# GPS_radiologger_v20.net
KiCad netlist of a schematic drawn in EAGLE
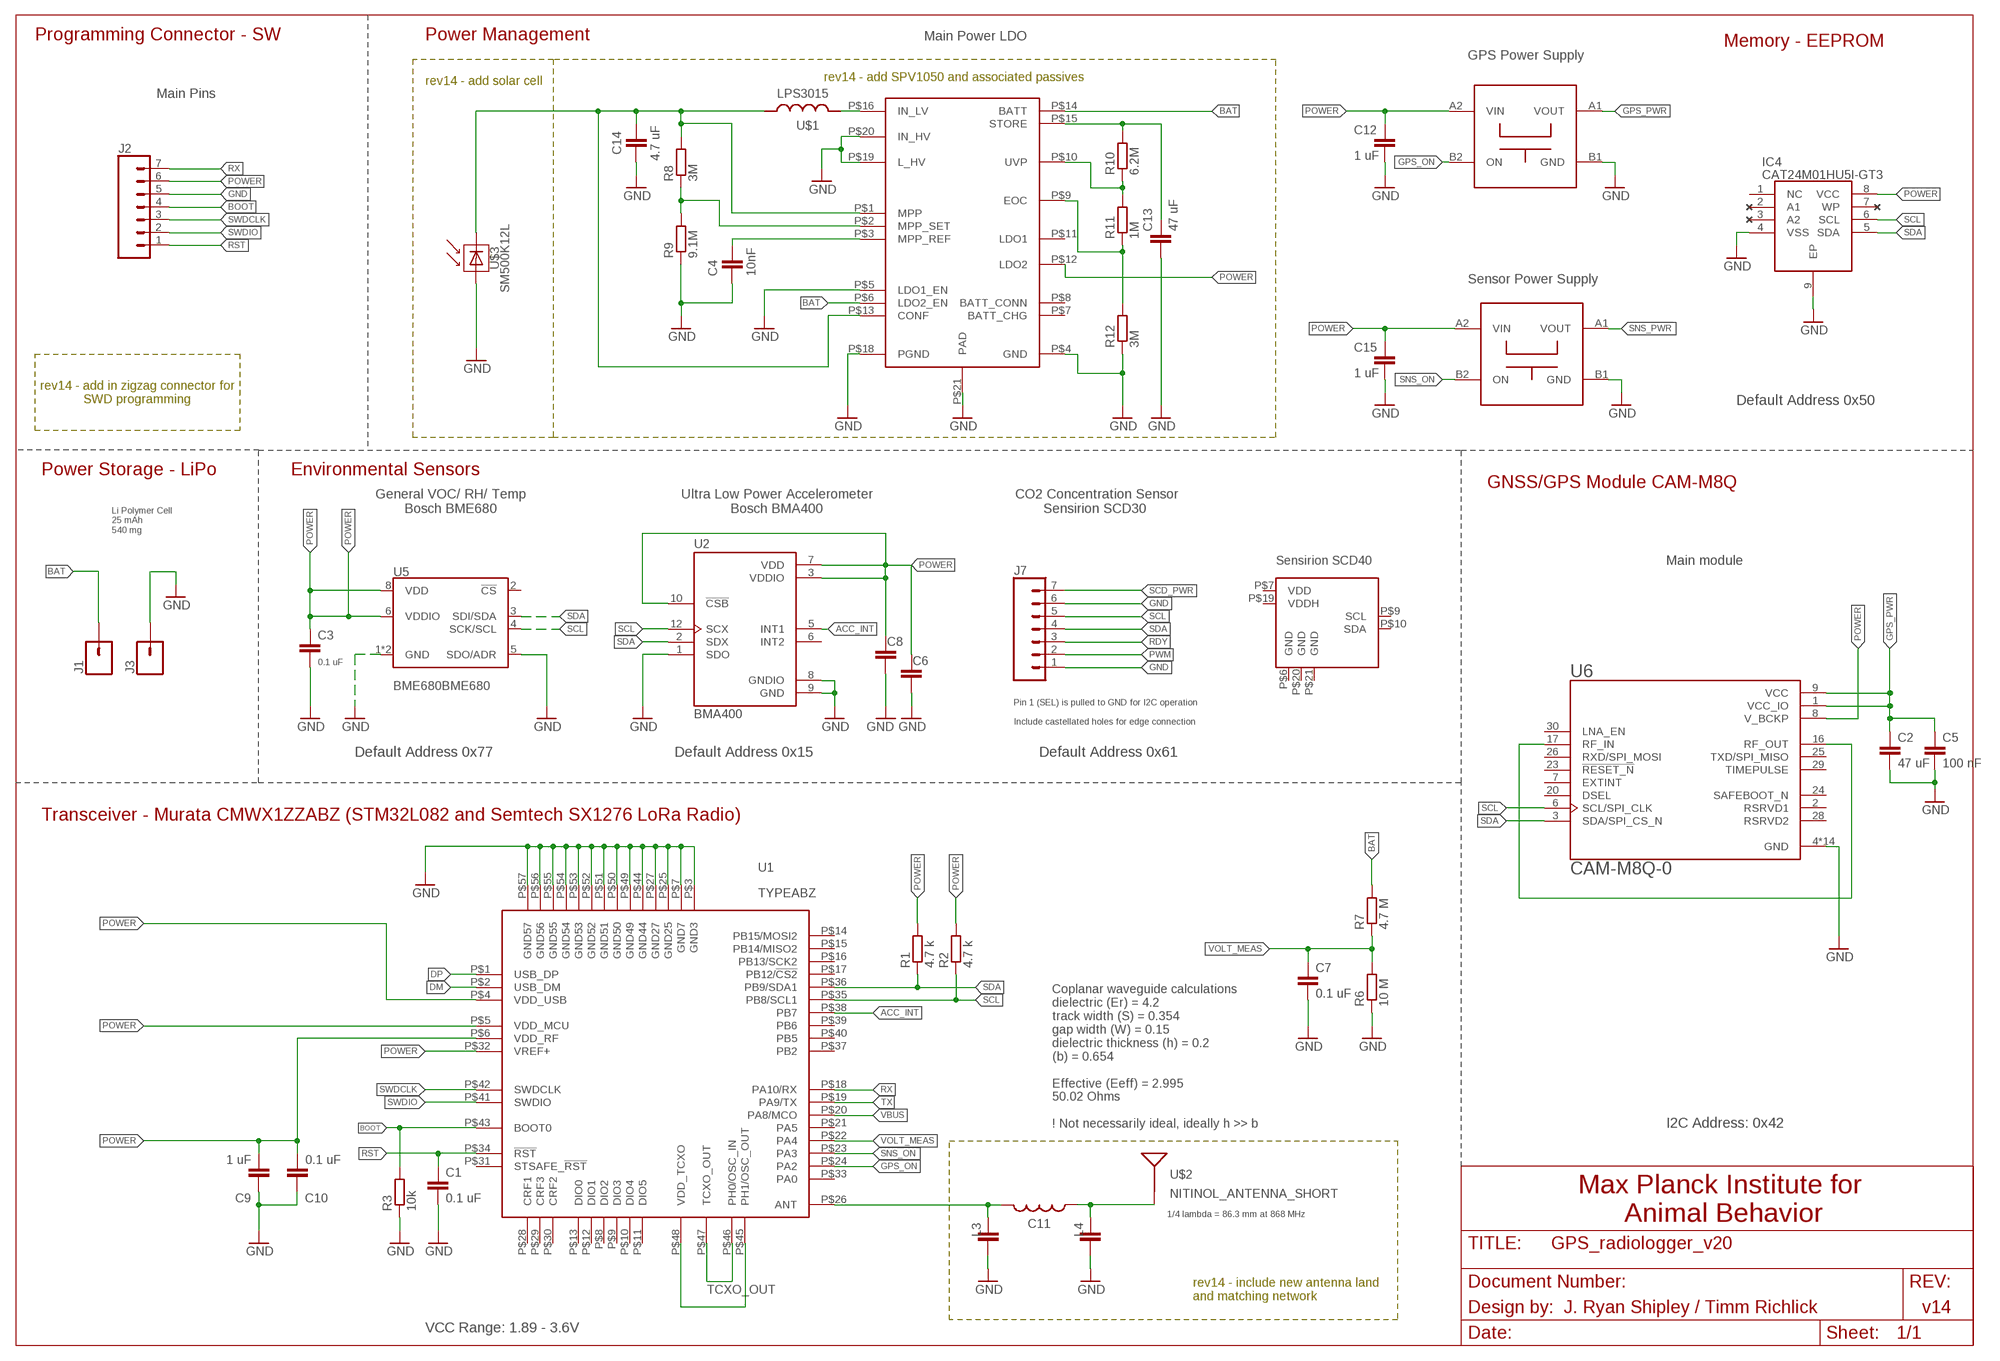
[diagram p0: schematic, sheet 1]

(export (version "E")
  (design (tool "Eeschema 10.0.6"))
  (components
    (comp (ref "C1")
      (value "0.1 uF")
      (footprint "eagle-import:C0201")
      (libsource (lib "eagle-import") (part "C-EUC0201"))
    )
    (comp (ref "C2")
      (value "47 uF")
      (footprint "eagle-import:C0201")
      (libsource (lib "eagle-import") (part "C-EUC0201"))
    )
    (comp (ref "C3")
      (value "0.1 uF")
      (footprint "eagle-import:C0201")
      (libsource (lib "eagle-import") (part "C-EUC0201"))
    )
    (comp (ref "C4")
      (value "10nF")
      (footprint "eagle-import:C0201")
      (libsource (lib "eagle-import") (part "C-EUC0201"))
    )
    (comp (ref "C5")
      (value "100 nF")
      (footprint "eagle-import:C0201")
      (libsource (lib "eagle-import") (part "C-EUC0201"))
    )
    (comp (ref "C6")
      (value "C-EUC0201")
      (footprint "eagle-import:C0201")
      (libsource (lib "eagle-import") (part "C-EUC0201"))
    )
    (comp (ref "C7")
      (value "0.1 uF")
      (footprint "eagle-import:C0201")
      (libsource (lib "eagle-import") (part "C-EUC0201"))
    )
    (comp (ref "C8")
      (value "C-EUC0201")
      (footprint "eagle-import:C0201")
      (libsource (lib "eagle-import") (part "C-EUC0201"))
    )
    (comp (ref "C9")
      (value "1 uF")
      (footprint "eagle-import:C0201")
      (libsource (lib "eagle-import") (part "C-EUC0201"))
    )
    (comp (ref "C10")
      (value "0.1 uF")
      (footprint "eagle-import:C0201")
      (libsource (lib "eagle-import") (part "C-EUC0201"))
    )
    (comp (ref "C11")
      (value "0.1uF")
      (footprint "eagle-import:L0201")
      (libsource (lib "eagle-import") (part "L-USL0201"))
    )
    (comp (ref "C12")
      (value "1 uF")
      (footprint "eagle-import:C0201")
      (libsource (lib "eagle-import") (part "C-EUC0201"))
    )
    (comp (ref "C13")
      (value "47 uF")
      (footprint "eagle-import:C0805K")
      (libsource (lib "eagle-import") (part "C-EUC0805K"))
    )
    (comp (ref "C14")
      (value "4.7 uF")
      (footprint "eagle-import:C0201")
      (libsource (lib "eagle-import") (part "C-EUC0201"))
    )
    (comp (ref "C15")
      (value "1 uF")
      (footprint "eagle-import:C0201")
      (libsource (lib "eagle-import") (part "C-EUC0201"))
    )
    (comp (ref "IC4")
      (value "CAT24M01HU5I-GT3")
      (footprint "eagle-import:SON50P300X200X55-9N")
      (fields
        (field (name "MOUSER_PART_NUMBER") "863-CAT24M01HU5I-GT3")
        (field (name "RS_PART_NUMBER") "7814831P")
      )
      (libsource (lib "eagle-import") (part "CAT24M01HU5I-GT3"))
    )
    (comp (ref "J1")
      (value "CONN_01PTH_NO_SILK_YES_STOP")
      (footprint "eagle-import:1X01_NO_SILK")
      (libsource (lib "eagle-import") (part "CONN_01PTH_NO_SILK_YES_STOP"))
    )
    (comp (ref "J2")
      (value "CONN_07NO_SILK")
      (footprint "eagle-import:1X07_NO_SILK")
      (libsource (lib "eagle-import") (part "CONN_07NO_SILK"))
    )
    (comp (ref "J3")
      (value "CONN_01PTH_NO_SILK_YES_STOP")
      (footprint "eagle-import:1X01_NO_SILK")
      (libsource (lib "eagle-import") (part "CONN_01PTH_NO_SILK_YES_STOP"))
    )
    (comp (ref "J7")
      (value "CONN_07NO_SILK")
      (footprint "eagle-import:1X07_NO_SILK")
      (libsource (lib "eagle-import") (part "CONN_07NO_SILK"))
    )
    (comp (ref "L3")
      (value "C-EUC0201")
      (footprint "eagle-import:C0201")
      (libsource (lib "eagle-import") (part "C-EUC0201"))
    )
    (comp (ref "L4")
      (value "C-EUC0201")
      (footprint "eagle-import:C0201")
      (libsource (lib "eagle-import") (part "C-EUC0201"))
    )
    (comp (ref "R1")
      (value "4.7 k")
      (footprint "eagle-import:R0201")
      (libsource (lib "eagle-import") (part "R-EU_R0201"))
    )
    (comp (ref "R2")
      (value "4.7 k")
      (footprint "eagle-import:R0201")
      (libsource (lib "eagle-import") (part "R-EU_R0201"))
    )
    (comp (ref "R3")
      (value "10k")
      (footprint "eagle-import:R0201")
      (libsource (lib "eagle-import") (part "R-EU_R0201"))
    )
    (comp (ref "R6")
      (value "10 M")
      (footprint "eagle-import:R0201")
      (libsource (lib "eagle-import") (part "R-EU_R0201"))
    )
    (comp (ref "R7")
      (value "4.7 M")
      (footprint "eagle-import:R0201")
      (libsource (lib "eagle-import") (part "R-EU_R0201"))
    )
    (comp (ref "R8")
      (value "3M")
      (footprint "eagle-import:R0201")
      (libsource (lib "eagle-import") (part "R-EU_R0201"))
    )
    (comp (ref "R9")
      (value "9.1M")
      (footprint "eagle-import:R0201")
      (libsource (lib "eagle-import") (part "R-EU_R0201"))
    )
    (comp (ref "R10")
      (value "6.2M")
      (footprint "eagle-import:R0201")
      (libsource (lib "eagle-import") (part "R-EU_R0201"))
    )
    (comp (ref "R11")
      (value "1M")
      (footprint "eagle-import:R0201")
      (libsource (lib "eagle-import") (part "R-EU_R0201"))
    )
    (comp (ref "R12")
      (value "3M")
      (footprint "eagle-import:R0201")
      (libsource (lib "eagle-import") (part "R-EU_R0201"))
    )
    (comp (ref "U$1")
      (value "LPS3015")
      (footprint "eagle-import:LPS_3015")
      (libsource (lib "eagle-import") (part "LPS3015"))
    )
    (comp (ref "U$2")
      (value "NITINOL_ANTENNA_SHORT")
      (footprint "eagle-import:ICARUS_NITINOL_ANTENNA_SHORT")
      (libsource (lib "eagle-import") (part "NITINOL_ANTENNA_SHORT"))
    )
    (comp (ref "U$3")
      (value "SM500K12L")
      (footprint "eagle-import:SM500K12L")
      (libsource (lib "eagle-import") (part "SM500K12L"))
    )
    (comp (ref "U$4")
      (value "TPS22916CL")
      (footprint "eagle-import:YFP0004-DSBGA")
      (libsource (lib "eagle-import") (part "TPS22916CL"))
    )
    (comp (ref "U$5")
      (value "TPS22916CL")
      (footprint "eagle-import:YFP0004-DSBGA")
      (libsource (lib "eagle-import") (part "TPS22916CL"))
    )
    (comp (ref "U$6")
      (value "SCD40")
      (footprint "eagle-import:SCD40_LGA")
      (libsource (lib "eagle-import") (part "SCD40"))
    )
    (comp (ref "U1")
      (value "TYPEABZ")
      (footprint "eagle-import:TYPEABZ")
      (libsource (lib "eagle-import") (part "TYPEABZ"))
    )
    (comp (ref "U2")
      (value "BMA400")
      (footprint "eagle-import:XDCR_BMA400")
      (fields (field (name "MF") "Bosch Sensortec"))
      (libsource (lib "eagle-import") (part "BMA400"))
    )
    (comp (ref "U4")
      (value "SPV1050")
      (footprint "eagle-import:SPV1050")
      (libsource (lib "eagle-import") (part "SPV1050"))
    )
    (comp (ref "U5")
      (value "BME680BME680")
      (footprint "eagle-import:LGA3.0X3.0")
      (libsource (lib "eagle-import") (part "BME680BME680"))
    )
    (comp (ref "U6")
      (value "CAM-M8Q-0")
      (footprint "eagle-import:LCC100P960X1400X210-31N")
      (fields (field (name "MF") "U-Blox America"))
      (libsource (lib "eagle-import") (part "CAM-M8Q-0"))
    )
  )
  (nets
    (net (code "1") (name "/TCXO_OUT") (class "Default")
      (node (ref "U1") (pin "P$46") (pinfunction "PH0/OSC_IN_P$46") (pintype "bidirectional"))
      (node (ref "U1") (pin "P$47") (pinfunction "TCXO_OUT_P$47") (pintype "bidirectional"))
    )
    (net (code "2") (name "ACC_INT") (class "Default")
      (node (ref "U1") (pin "P$38") (pinfunction "PB7_P$38") (pintype "bidirectional"))
      (node (ref "U2") (pin "5") (pinfunction "INT1_5") (pintype "bidirectional"))
    )
    (net (code "3") (name "BAT") (class "Default")
      (node (ref "J1") (pin "1") (pinfunction "1_1") (pintype "passive"))
      (node (ref "R7") (pin "2") (pinfunction "2_2") (pintype "passive"))
      (node (ref "U4") (pin "P$14") (pinfunction "BATT_P$14") (pintype "bidirectional"))
      (node (ref "U4") (pin "P$6") (pinfunction "LDO2_EN_P$6") (pintype "input"))
    )
    (net (code "4") (name "BOOT") (class "Default")
      (node (ref "J2") (pin "4") (pinfunction "4_4") (pintype "passive"))
      (node (ref "R3") (pin "2") (pinfunction "2_2") (pintype "passive"))
      (node (ref "U1") (pin "P$43") (pinfunction "BOOT0_P$43") (pintype "bidirectional"))
    )
    (net (code "5") (name "DM") (class "Default")
      (node (ref "U1") (pin "P$2") (pinfunction "USB_DM_P$2") (pintype "bidirectional"))
    )
    (net (code "6") (name "DP") (class "Default")
      (node (ref "U1") (pin "P$1") (pinfunction "USB_DP_P$1") (pintype "bidirectional"))
    )
    (net (code "7") (name "GND") (class "Default")
      (node (ref "C1") (pin "2") (pinfunction "2_2") (pintype "passive"))
      (node (ref "C10") (pin "1") (pinfunction "1_1") (pintype "passive"))
      (node (ref "C12") (pin "2") (pinfunction "2_2") (pintype "passive"))
      (node (ref "C13") (pin "2") (pinfunction "2_2") (pintype "passive"))
      (node (ref "C14") (pin "2") (pinfunction "2_2") (pintype "passive"))
      (node (ref "C15") (pin "2") (pinfunction "2_2") (pintype "passive"))
      (node (ref "C2") (pin "2") (pinfunction "2_2") (pintype "passive"))
      (node (ref "C3") (pin "2") (pinfunction "2_2") (pintype "passive"))
      (node (ref "C4") (pin "2") (pinfunction "2_2") (pintype "passive"))
      (node (ref "C5") (pin "2") (pinfunction "2_2") (pintype "passive"))
      (node (ref "C6") (pin "2") (pinfunction "2_2") (pintype "passive"))
      (node (ref "C7") (pin "2") (pinfunction "2_2") (pintype "passive"))
      (node (ref "C8") (pin "2") (pinfunction "2_2") (pintype "passive"))
      (node (ref "C9") (pin "1") (pinfunction "1_1") (pintype "passive"))
      (node (ref "IC4") (pin "4") (pinfunction "VSS_4") (pintype "power_in"))
      (node (ref "IC4") (pin "9") (pinfunction "EP_9") (pintype "bidirectional"))
      (node (ref "J2") (pin "5") (pinfunction "5_5") (pintype "passive"))
      (node (ref "J3") (pin "1") (pinfunction "1_1") (pintype "passive"))
      (node (ref "J7") (pin "1") (pinfunction "1_1") (pintype "passive"))
      (node (ref "J7") (pin "6") (pinfunction "6_6") (pintype "passive"))
      (node (ref "L3") (pin "2") (pinfunction "2_2") (pintype "passive"))
      (node (ref "L4") (pin "2") (pinfunction "2_2") (pintype "passive"))
      (node (ref "R12") (pin "1") (pinfunction "1_1") (pintype "passive"))
      (node (ref "R3") (pin "1") (pinfunction "1_1") (pintype "passive"))
      (node (ref "R6") (pin "1") (pinfunction "1_1") (pintype "passive"))
      (node (ref "R9") (pin "1") (pinfunction "1_1") (pintype "passive"))
      (node (ref "U$3") (pin "P$2") (pinfunction "MINUS_P$2") (pintype "passive"))
      (node (ref "U$4") (pin "B1") (pinfunction "GND_B1") (pintype "bidirectional"))
      (node (ref "U$5") (pin "B1") (pinfunction "GND_B1") (pintype "bidirectional"))
      (node (ref "U1") (pin "P$25") (pinfunction "GND25_P$25") (pintype "power_in"))
      (node (ref "U1") (pin "P$27") (pinfunction "GND27_P$27") (pintype "power_in"))
      (node (ref "U1") (pin "P$3") (pinfunction "GND3_P$3") (pintype "power_in"))
      (node (ref "U1") (pin "P$44") (pinfunction "GND44_P$44") (pintype "power_in"))
      (node (ref "U1") (pin "P$49") (pinfunction "GND49_P$49") (pintype "power_in"))
      (node (ref "U1") (pin "P$50") (pinfunction "GND50_P$50") (pintype "power_in"))
      (node (ref "U1") (pin "P$51") (pinfunction "GND51_P$51") (pintype "power_in"))
      (node (ref "U1") (pin "P$52") (pinfunction "GND52_P$52") (pintype "power_in"))
      (node (ref "U1") (pin "P$53") (pinfunction "GND53_P$53") (pintype "power_in"))
      (node (ref "U1") (pin "P$54") (pinfunction "GND54_P$54") (pintype "power_in"))
      (node (ref "U1") (pin "P$55") (pinfunction "GND55_P$55") (pintype "power_in"))
      (node (ref "U1") (pin "P$56") (pinfunction "GND56_P$56") (pintype "power_in"))
      (node (ref "U1") (pin "P$57") (pinfunction "GND57_P$57") (pintype "power_in"))
      (node (ref "U1") (pin "P$7") (pinfunction "GND7_P$7") (pintype "power_in"))
      (node (ref "U2") (pin "1") (pinfunction "SDO_1") (pintype "bidirectional"))
      (node (ref "U2") (pin "8") (pinfunction "GNDIO_8") (pintype "power_in"))
      (node (ref "U2") (pin "9") (pinfunction "GND_9") (pintype "power_in"))
      (node (ref "U4") (pin "P$18") (pinfunction "PGND_P$18") (pintype "power_in"))
      (node (ref "U4") (pin "P$19") (pinfunction "L_HV_P$19") (pintype "power_in"))
      (node (ref "U4") (pin "P$20") (pinfunction "IN_HV_P$20") (pintype "power_in"))
      (node (ref "U4") (pin "P$21") (pinfunction "PAD_P$21") (pintype "power_in"))
      (node (ref "U4") (pin "P$4") (pinfunction "GND_P$4") (pintype "power_in"))
      (node (ref "U4") (pin "P$5") (pinfunction "LDO1_EN_P$5") (pintype "input"))
      (node (ref "U5") (pin "1") (pinfunction "GND_1") (pintype "bidirectional"))
      (node (ref "U5") (pin "5") (pinfunction "SDO/ADR_5") (pintype "bidirectional"))
      (node (ref "U5") (pin "7") (pinfunction "GND_7") (pintype "bidirectional"))
      (node (ref "U6") (pin "10") (pinfunction "GND_10") (pintype "power_in"))
      (node (ref "U6") (pin "11") (pinfunction "GND_11") (pintype "power_in"))
      (node (ref "U6") (pin "12") (pinfunction "GND_12") (pintype "power_in"))
      (node (ref "U6") (pin "13") (pinfunction "GND_13") (pintype "power_in"))
      (node (ref "U6") (pin "14") (pinfunction "GND_14") (pintype "power_in"))
      (node (ref "U6") (pin "15") (pinfunction "GND_15") (pintype "power_in"))
      (node (ref "U6") (pin "18") (pinfunction "GND_18") (pintype "power_in"))
      (node (ref "U6") (pin "19") (pinfunction "GND_19") (pintype "power_in"))
      (node (ref "U6") (pin "21") (pinfunction "GND_21") (pintype "power_in"))
      (node (ref "U6") (pin "22") (pinfunction "GND_22") (pintype "power_in"))
      (node (ref "U6") (pin "27") (pinfunction "GND_27") (pintype "power_in"))
      (node (ref "U6") (pin "31") (pinfunction "GND_31") (pintype "power_in"))
      (node (ref "U6") (pin "4") (pinfunction "GND_4") (pintype "power_in"))
      (node (ref "U6") (pin "5") (pinfunction "GND_5") (pintype "power_in"))
    )
    (net (code "8") (name "GPS_ON") (class "Default")
      (node (ref "U$4") (pin "B2") (pinfunction "ON_B2") (pintype "bidirectional"))
      (node (ref "U1") (pin "P$24") (pinfunction "PA2_P$24") (pintype "bidirectional"))
    )
    (net (code "9") (name "GPS_PWR") (class "Default")
      (node (ref "C2") (pin "1") (pinfunction "1_1") (pintype "passive"))
      (node (ref "C5") (pin "1") (pinfunction "1_1") (pintype "passive"))
      (node (ref "U$4") (pin "A1") (pinfunction "VOUT_A1") (pintype "bidirectional"))
      (node (ref "U6") (pin "1") (pinfunction "VCC_IO_1") (pintype "power_in"))
      (node (ref "U6") (pin "9") (pinfunction "VCC_9") (pintype "power_in"))
    )
    (net (code "10") (name "Net-(C11-Pad1)") (class "Default")
      (node (ref "C11") (pin "1") (pinfunction "1_1") (pintype "passive"))
      (node (ref "L4") (pin "1") (pinfunction "1_1") (pintype "passive"))
      (node (ref "U$2") (pin "1") (pinfunction "SIGNAL_1") (pintype "bidirectional"))
      (node (ref "U$2") (pin "2") (pinfunction "SIGNAL_2") (pintype "bidirectional"))
      (node (ref "U$2") (pin "3") (pinfunction "SIGNAL_3") (pintype "bidirectional"))
    )
    (net (code "11") (name "Net-(U$1-1)") (class "Default")
      (node (ref "C14") (pin "1") (pinfunction "1_1") (pintype "passive"))
      (node (ref "R8") (pin "2") (pinfunction "2_2") (pintype "passive"))
      (node (ref "U$1") (pin "P$1") (pinfunction "1_P$1") (pintype "passive"))
      (node (ref "U$3") (pin "P$1") (pinfunction "PLUS_P$1") (pintype "passive"))
      (node (ref "U4") (pin "P$1") (pinfunction "MPP_P$1") (pintype "input"))
      (node (ref "U4") (pin "P$13") (pinfunction "CONF_P$13") (pintype "input"))
    )
    (net (code "12") (name "Net-(U$1-2)") (class "Default")
      (node (ref "U$1") (pin "P$2") (pinfunction "2_P$2") (pintype "passive"))
      (node (ref "U4") (pin "P$16") (pinfunction "IN_LV_P$16") (pintype "power_in"))
    )
    (net (code "13") (name "Net-(U1-ANT)") (class "Default")
      (node (ref "C11") (pin "2") (pinfunction "2_2") (pintype "passive"))
      (node (ref "L3") (pin "1") (pinfunction "1_1") (pintype "passive"))
      (node (ref "U1") (pin "P$26") (pinfunction "ANT_P$26") (pintype "bidirectional"))
    )
    (net (code "14") (name "Net-(U1-PH1{slash}OSC_OUT)") (class "Default")
      (node (ref "U1") (pin "P$45") (pinfunction "PH1/OSC_OUT_P$45") (pintype "bidirectional"))
      (node (ref "U1") (pin "P$48") (pinfunction "VDD_TCXO_P$48") (pintype "power_in"))
    )
    (net (code "15") (name "Net-(U4-EOC)") (class "Default")
      (node (ref "R11") (pin "1") (pinfunction "1_1") (pintype "passive"))
      (node (ref "R12") (pin "2") (pinfunction "2_2") (pintype "passive"))
      (node (ref "U4") (pin "P$9") (pinfunction "EOC_P$9") (pintype "input"))
    )
    (net (code "16") (name "Net-(U4-MPP_REF)") (class "Default")
      (node (ref "C4") (pin "1") (pinfunction "1_1") (pintype "passive"))
      (node (ref "U4") (pin "P$3") (pinfunction "MPP_REF_P$3") (pintype "input"))
    )
    (net (code "17") (name "Net-(U4-MPP_SET)") (class "Default")
      (node (ref "R8") (pin "1") (pinfunction "1_1") (pintype "passive"))
      (node (ref "R9") (pin "2") (pinfunction "2_2") (pintype "passive"))
      (node (ref "U4") (pin "P$2") (pinfunction "MPP_SET_P$2") (pintype "input"))
    )
    (net (code "18") (name "Net-(U4-STORE)") (class "Default")
      (node (ref "C13") (pin "1") (pinfunction "1_1") (pintype "passive"))
      (node (ref "R10") (pin "2") (pinfunction "2_2") (pintype "passive"))
      (node (ref "U4") (pin "P$15") (pinfunction "STORE_P$15") (pintype "bidirectional"))
    )
    (net (code "19") (name "Net-(U4-UVP)") (class "Default")
      (node (ref "R10") (pin "1") (pinfunction "1_1") (pintype "passive"))
      (node (ref "R11") (pin "2") (pinfunction "2_2") (pintype "passive"))
      (node (ref "U4") (pin "P$10") (pinfunction "UVP_P$10") (pintype "input"))
    )
    (net (code "20") (name "Net-(U6-RF_IN)") (class "Default")
      (node (ref "U6") (pin "16") (pinfunction "RF_OUT_16") (pintype "output"))
      (node (ref "U6") (pin "17") (pinfunction "RF_IN_17") (pintype "input"))
    )
    (net (code "21") (name "POWER") (class "Default")
      (node (ref "C10") (pin "2") (pinfunction "2_2") (pintype "passive"))
      (node (ref "C12") (pin "1") (pinfunction "1_1") (pintype "passive"))
      (node (ref "C15") (pin "1") (pinfunction "1_1") (pintype "passive"))
      (node (ref "C3") (pin "1") (pinfunction "1_1") (pintype "passive"))
      (node (ref "C6") (pin "1") (pinfunction "1_1") (pintype "passive"))
      (node (ref "C8") (pin "1") (pinfunction "1_1") (pintype "passive"))
      (node (ref "C9") (pin "2") (pinfunction "2_2") (pintype "passive"))
      (node (ref "IC4") (pin "8") (pinfunction "VCC_8") (pintype "power_in"))
      (node (ref "J2") (pin "6") (pinfunction "6_6") (pintype "passive"))
      (node (ref "R1") (pin "2") (pinfunction "2_2") (pintype "passive"))
      (node (ref "R2") (pin "2") (pinfunction "2_2") (pintype "passive"))
      (node (ref "U$4") (pin "A2") (pinfunction "VIN_A2") (pintype "bidirectional"))
      (node (ref "U$5") (pin "A2") (pinfunction "VIN_A2") (pintype "bidirectional"))
      (node (ref "U1") (pin "P$32") (pinfunction "VREF+_P$32") (pintype "power_in"))
      (node (ref "U1") (pin "P$4") (pinfunction "VDD_USB_P$4") (pintype "power_in"))
      (node (ref "U1") (pin "P$5") (pinfunction "VDD_MCU_P$5") (pintype "power_in"))
      (node (ref "U1") (pin "P$6") (pinfunction "VDD_RF_P$6") (pintype "power_in"))
      (node (ref "U2") (pin "10") (pinfunction "~{CSB}_10") (pintype "input"))
      (node (ref "U2") (pin "3") (pinfunction "VDDIO_3") (pintype "power_in"))
      (node (ref "U2") (pin "7") (pinfunction "VDD_7") (pintype "power_in"))
      (node (ref "U4") (pin "P$12") (pinfunction "LDO2_P$12") (pintype "output"))
      (node (ref "U5") (pin "6") (pinfunction "VDDIO_6") (pintype "bidirectional"))
      (node (ref "U5") (pin "8") (pinfunction "VDD_8") (pintype "bidirectional"))
      (node (ref "U6") (pin "8") (pinfunction "V_BCKP_8") (pintype "power_in"))
    )
    (net (code "22") (name "PWM") (class "Default")
      (node (ref "J7") (pin "2") (pinfunction "2_2") (pintype "passive"))
    )
    (net (code "23") (name "RDY") (class "Default")
      (node (ref "J7") (pin "3") (pinfunction "3_3") (pintype "passive"))
    )
    (net (code "24") (name "RST") (class "Default")
      (node (ref "C1") (pin "1") (pinfunction "1_1") (pintype "passive"))
      (node (ref "J2") (pin "1") (pinfunction "1_1") (pintype "passive"))
      (node (ref "U1") (pin "P$34") (pinfunction "~{RST}_P$34") (pintype "bidirectional"))
    )
    (net (code "25") (name "RX") (class "Default")
      (node (ref "J2") (pin "7") (pinfunction "7_7") (pintype "passive"))
      (node (ref "U1") (pin "P$18") (pinfunction "PA10/RX_P$18") (pintype "bidirectional"))
    )
    (net (code "26") (name "SCD_PWR") (class "Default")
      (node (ref "J7") (pin "7") (pinfunction "7_7") (pintype "passive"))
    )
    (net (code "27") (name "SCL") (class "Default")
      (node (ref "IC4") (pin "6") (pinfunction "SCL_6") (pintype "bidirectional"))
      (node (ref "J7") (pin "5") (pinfunction "5_5") (pintype "passive"))
      (node (ref "R2") (pin "1") (pinfunction "1_1") (pintype "passive"))
      (node (ref "U1") (pin "P$35") (pinfunction "PB8/SCL1_P$35") (pintype "bidirectional"))
      (node (ref "U2") (pin "12") (pinfunction "SCX_12") (pintype "input"))
      (node (ref "U5") (pin "4") (pinfunction "SCK/SCL_4") (pintype "bidirectional"))
      (node (ref "U6") (pin "6") (pinfunction "SCL/SPI_CLK_6") (pintype "input"))
    )
    (net (code "28") (name "SDA") (class "Default")
      (node (ref "IC4") (pin "5") (pinfunction "SDA_5") (pintype "bidirectional"))
      (node (ref "J7") (pin "4") (pinfunction "4_4") (pintype "passive"))
      (node (ref "R1") (pin "1") (pinfunction "1_1") (pintype "passive"))
      (node (ref "U1") (pin "P$36") (pinfunction "PB9/SDA1_P$36") (pintype "bidirectional"))
      (node (ref "U2") (pin "2") (pinfunction "SDX_2") (pintype "bidirectional"))
      (node (ref "U5") (pin "3") (pinfunction "SDI/SDA_3") (pintype "bidirectional"))
      (node (ref "U6") (pin "3") (pinfunction "SDA/SPI_CS_N_3") (pintype "bidirectional"))
    )
    (net (code "29") (name "SNS_ON") (class "Default")
      (node (ref "U$5") (pin "B2") (pinfunction "ON_B2") (pintype "bidirectional"))
      (node (ref "U1") (pin "P$23") (pinfunction "PA3_P$23") (pintype "bidirectional"))
    )
    (net (code "30") (name "SNS_PWR") (class "Default")
      (node (ref "U$5") (pin "A1") (pinfunction "VOUT_A1") (pintype "bidirectional"))
    )
    (net (code "31") (name "SWDCLK") (class "Default")
      (node (ref "J2") (pin "3") (pinfunction "3_3") (pintype "passive"))
      (node (ref "U1") (pin "P$42") (pinfunction "SWDCLK_P$42") (pintype "bidirectional"))
    )
    (net (code "32") (name "SWDIO") (class "Default")
      (node (ref "J2") (pin "2") (pinfunction "2_2") (pintype "passive"))
      (node (ref "U1") (pin "P$41") (pinfunction "SWDIO_P$41") (pintype "bidirectional"))
    )
    (net (code "33") (name "TX") (class "Default")
      (node (ref "U1") (pin "P$19") (pinfunction "PA9/TX_P$19") (pintype "bidirectional"))
    )
    (net (code "34") (name "VBUS") (class "Default")
      (node (ref "U1") (pin "P$20") (pinfunction "PA8/MCO_P$20") (pintype "bidirectional"))
    )
    (net (code "35") (name "VOLT_MEAS") (class "Default")
      (node (ref "C7") (pin "1") (pinfunction "1_1") (pintype "passive"))
      (node (ref "R6") (pin "2") (pinfunction "2_2") (pintype "passive"))
      (node (ref "R7") (pin "1") (pinfunction "1_1") (pintype "passive"))
      (node (ref "U1") (pin "P$22") (pinfunction "PA4_P$22") (pintype "bidirectional"))
    )
    (net (code "36") (name "unconnected-(IC4-A1-Pad2)") (class "Default")
      (node (ref "IC4") (pin "2") (pinfunction "A1_2") (pintype "bidirectional"))
    )
    (net (code "37") (name "unconnected-(IC4-A2-Pad3)") (class "Default")
      (node (ref "IC4") (pin "3") (pinfunction "A2_3") (pintype "bidirectional"))
    )
    (net (code "38") (name "unconnected-(IC4-NC-Pad1)") (class "Default")
      (node (ref "IC4") (pin "1") (pinfunction "NC_1") (pintype "no_connect"))
    )
    (net (code "39") (name "unconnected-(IC4-WP-Pad7)") (class "Default")
      (node (ref "IC4") (pin "7") (pinfunction "WP_7") (pintype "bidirectional"))
    )
    (net (code "40") (name "unconnected-(U$6-GND-PadP$6)") (class "Default")
      (node (ref "U$6") (pin "P$6") (pinfunction "GND_P$6") (pintype "bidirectional"))
    )
    (net (code "41") (name "unconnected-(U$6-GND-PadP$20)") (class "Default")
      (node (ref "U$6") (pin "P$20") (pinfunction "GND_P$20") (pintype "bidirectional"))
    )
    (net (code "42") (name "unconnected-(U$6-GND-PadP$21)") (class "Default")
      (node (ref "U$6") (pin "P$21") (pinfunction "GND_P$21") (pintype "bidirectional"))
    )
    (net (code "43") (name "unconnected-(U$6-SCL-PadP$9)") (class "Default")
      (node (ref "U$6") (pin "P$9") (pinfunction "SCL_P$9") (pintype "bidirectional"))
    )
    (net (code "44") (name "unconnected-(U$6-SDA-PadP$10)") (class "Default")
      (node (ref "U$6") (pin "P$10") (pinfunction "SDA_P$10") (pintype "bidirectional"))
    )
    (net (code "45") (name "unconnected-(U$6-VDD-PadP$7)") (class "Default")
      (node (ref "U$6") (pin "P$7") (pinfunction "VDD_P$7") (pintype "bidirectional"))
    )
    (net (code "46") (name "unconnected-(U$6-VDDH-PadP$19)") (class "Default")
      (node (ref "U$6") (pin "P$19") (pinfunction "VDDH_P$19") (pintype "bidirectional"))
    )
    (net (code "47") (name "unconnected-(U1-CRF1-PadP$28)") (class "Default")
      (node (ref "U1") (pin "P$28") (pinfunction "CRF1_P$28") (pintype "no_connect"))
    )
    (net (code "48") (name "unconnected-(U1-CRF2-PadP$30)") (class "Default")
      (node (ref "U1") (pin "P$30") (pinfunction "CRF2_P$30") (pintype "no_connect"))
    )
    (net (code "49") (name "unconnected-(U1-CRF3-PadP$29)") (class "Default")
      (node (ref "U1") (pin "P$29") (pinfunction "CRF3_P$29") (pintype "no_connect"))
    )
    (net (code "50") (name "unconnected-(U1-DIO0-PadP$13)") (class "Default")
      (node (ref "U1") (pin "P$13") (pinfunction "DIO0_P$13") (pintype "no_connect"))
    )
    (net (code "51") (name "unconnected-(U1-DIO1-PadP$12)") (class "Default")
      (node (ref "U1") (pin "P$12") (pinfunction "DIO1_P$12") (pintype "no_connect"))
    )
    (net (code "52") (name "unconnected-(U1-DIO2-PadP$8)") (class "Default")
      (node (ref "U1") (pin "P$8") (pinfunction "DIO2_P$8") (pintype "no_connect"))
    )
    (net (code "53") (name "unconnected-(U1-DIO3-PadP$9)") (class "Default")
      (node (ref "U1") (pin "P$9") (pinfunction "DIO3_P$9") (pintype "no_connect"))
    )
    (net (code "54") (name "unconnected-(U1-DIO4-PadP$10)") (class "Default")
      (node (ref "U1") (pin "P$10") (pinfunction "DIO4_P$10") (pintype "bidirectional"))
    )
    (net (code "55") (name "unconnected-(U1-DIO5-PadP$11)") (class "Default")
      (node (ref "U1") (pin "P$11") (pinfunction "DIO5_P$11") (pintype "bidirectional"))
    )
    (net (code "56") (name "unconnected-(U1-PA0-PadP$33)") (class "Default")
      (node (ref "U1") (pin "P$33") (pinfunction "PA0_P$33") (pintype "bidirectional"))
    )
    (net (code "57") (name "unconnected-(U1-PA5-PadP$21)") (class "Default")
      (node (ref "U1") (pin "P$21") (pinfunction "PA5_P$21") (pintype "bidirectional"))
    )
    (net (code "58") (name "unconnected-(U1-PB2-PadP$37)") (class "Default")
      (node (ref "U1") (pin "P$37") (pinfunction "PB2_P$37") (pintype "bidirectional"))
    )
    (net (code "59") (name "unconnected-(U1-PB5-PadP$40)") (class "Default")
      (node (ref "U1") (pin "P$40") (pinfunction "PB5_P$40") (pintype "bidirectional"))
    )
    (net (code "60") (name "unconnected-(U1-PB6-PadP$39)") (class "Default")
      (node (ref "U1") (pin "P$39") (pinfunction "PB6_P$39") (pintype "bidirectional"))
    )
    (net (code "61") (name "unconnected-(U1-PB12{slash}~{CS2}-PadP$17)") (class "Default")
      (node (ref "U1") (pin "P$17") (pinfunction "PB12/~{CS2}_P$17") (pintype "bidirectional"))
    )
    (net (code "62") (name "unconnected-(U1-PB13{slash}SCK2-PadP$16)") (class "Default")
      (node (ref "U1") (pin "P$16") (pinfunction "PB13/SCK2_P$16") (pintype "bidirectional"))
    )
    (net (code "63") (name "unconnected-(U1-PB14{slash}MISO2-PadP$15)") (class "Default")
      (node (ref "U1") (pin "P$15") (pinfunction "PB14/MISO2_P$15") (pintype "bidirectional"))
    )
    (net (code "64") (name "unconnected-(U1-PB15{slash}MOSI2-PadP$14)") (class "Default")
      (node (ref "U1") (pin "P$14") (pinfunction "PB15/MOSI2_P$14") (pintype "bidirectional"))
    )
    (net (code "65") (name "unconnected-(U1-STSAFE_~{RST}-PadP$31)") (class "Default")
      (node (ref "U1") (pin "P$31") (pinfunction "STSAFE_~{RST}_P$31") (pintype "bidirectional"))
    )
    (net (code "66") (name "unconnected-(U2-INT2-Pad6)") (class "Default")
      (node (ref "U2") (pin "6") (pinfunction "INT2_6") (pintype "bidirectional"))
    )
    (net (code "67") (name "unconnected-(U4-BATT_CHG-PadP$7)") (class "Default")
      (node (ref "U4") (pin "P$7") (pinfunction "BATT_CHG_P$7") (pintype "open_collector"))
    )
    (net (code "68") (name "unconnected-(U4-BATT_CONN-PadP$8)") (class "Default")
      (node (ref "U4") (pin "P$8") (pinfunction "BATT_CONN_P$8") (pintype "open_collector"))
    )
    (net (code "69") (name "unconnected-(U4-LDO1-PadP$11)") (class "Default")
      (node (ref "U4") (pin "P$11") (pinfunction "LDO1_P$11") (pintype "output"))
    )
    (net (code "70") (name "unconnected-(U5-~{CS}-Pad2)") (class "Default")
      (node (ref "U5") (pin "2") (pinfunction "~{CS}_2") (pintype "bidirectional"))
    )
    (net (code "71") (name "unconnected-(U6-DSEL-Pad20)") (class "Default")
      (node (ref "U6") (pin "20") (pinfunction "DSEL_20") (pintype "input"))
    )
    (net (code "72") (name "unconnected-(U6-EXTINT-Pad7)") (class "Default")
      (node (ref "U6") (pin "7") (pinfunction "EXTINT_7") (pintype "input"))
    )
    (net (code "73") (name "unconnected-(U6-LNA_EN-Pad30)") (class "Default")
      (node (ref "U6") (pin "30") (pinfunction "LNA_EN_30") (pintype "input"))
    )
    (net (code "74") (name "unconnected-(U6-RSRVD1-Pad2)") (class "Default")
      (node (ref "U6") (pin "2") (pinfunction "RSRVD1_2") (pintype "passive"))
    )
    (net (code "75") (name "unconnected-(U6-RSRVD2-Pad28)") (class "Default")
      (node (ref "U6") (pin "28") (pinfunction "RSRVD2_28") (pintype "passive"))
    )
    (net (code "76") (name "unconnected-(U6-RXD{slash}SPI_MOSI-Pad26)") (class "Default")
      (node (ref "U6") (pin "26") (pinfunction "RXD/SPI_MOSI_26") (pintype "input"))
    )
    (net (code "77") (name "unconnected-(U6-SAFEBOOT_N-Pad24)") (class "Default")
      (node (ref "U6") (pin "24") (pinfunction "SAFEBOOT_N_24") (pintype "passive"))
    )
    (net (code "78") (name "unconnected-(U6-TIMEPULSE-Pad29)") (class "Default")
      (node (ref "U6") (pin "29") (pinfunction "TIMEPULSE_29") (pintype "output"))
    )
    (net (code "79") (name "unconnected-(U6-TXD{slash}SPI_MISO-Pad25)") (class "Default")
      (node (ref "U6") (pin "25") (pinfunction "TXD/SPI_MISO_25") (pintype "output"))
    )
    (net (code "80") (name "unconnected-(U6-~{RESET_N}-Pad23)") (class "Default")
      (node (ref "U6") (pin "23") (pinfunction "~{RESET_N}_23") (pintype "input"))
    )
  )
)
